# Led_Driver.net
KiCad netlist of a schematic drawn in Altium Designer
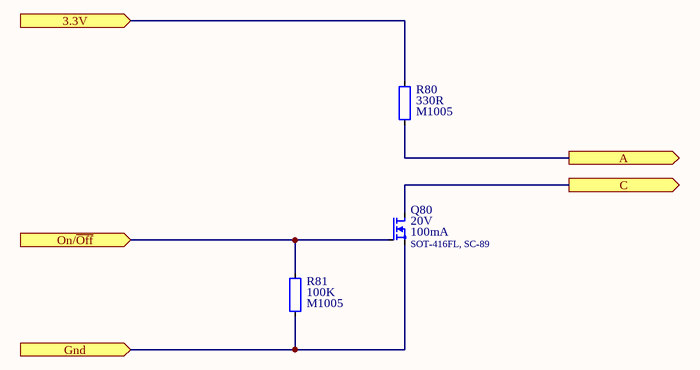
[diagram p0: Led Driver.SchDoc]

(export (version "E")
  (design (tool "Eeschema 10.0.6"))
  (components
    (comp (ref "Q80")
      (value "Mosfet, N-Channel")
      (footprint "SOT-416FL, Mosfet - Type 1")
      (description "MOSFET, N-CH, 20V, 100mA, SOT-416FL")
      (fields
        (field (name "MANUFACTURER PART NUMBER") "RE1C001UNTCL")
        (field (name "MANUFACTURER") "Rohm")
        (field (name "CURRENT") "100mA")
        (field (name "VOLTAGE") "20V")
        (field (name "PACKAGE") "SOT-416FL, SC-89")
      )
      (libsource (lib "Transistor") (part "Mosfet, N-Channel"))
    )
    (comp (ref "R80")
      (value "330R")
      (footprint "Resistor_Smd_M1005_I0402")
      (description "Res, 330R, 1%, M1005")
      (fields
        (field (name "TOLERANCE") "1%")
        (field (name "MANUFACTURER") "Yageo")
        (field (name "PACKAGE") "M1005")
      )
      (libsource (lib "Resistor") (part "Resistor"))
    )
    (comp (ref "R81")
      (value "100K")
      (footprint "Resistor_Smd_M1005_I0402")
      (description "Res, 100K, 1%, M1005")
      (fields
        (field (name "TOLERANCE") "1%")
        (field (name "MANUFACTURER") "Yageo")
        (field (name "PACKAGE") "M1005")
      )
      (libsource (lib "Resistor") (part "Resistor"))
    )
  )
  (nets
    (net (code "1") (name "/3.3V") (class "Default")
      (node (ref "R80") (pin "1") (pinfunction "1_1") (pintype "passive"))
    )
    (net (code "2") (name "/A") (class "Default")
      (node (ref "R80") (pin "2") (pinfunction "2_2") (pintype "passive"))
    )
    (net (code "3") (name "/C") (class "Default")
      (node (ref "Q80") (pin "D") (pinfunction "D_D") (pintype "passive"))
    )
    (net (code "4") (name "/Gnd") (class "Default")
      (node (ref "Q80") (pin "S") (pinfunction "S_S") (pintype "passive"))
      (node (ref "R81") (pin "2") (pinfunction "2_2") (pintype "passive"))
    )
    (net (code "5") (name "/On{slash}~{Off}") (class "Default")
      (node (ref "Q80") (pin "G") (pinfunction "G_G") (pintype "passive"))
      (node (ref "R81") (pin "1") (pinfunction "1_1") (pintype "passive"))
    )
  )
)
